# System_Voltage_Regulators.net
KiCad netlist of a schematic drawn in Altium Designer
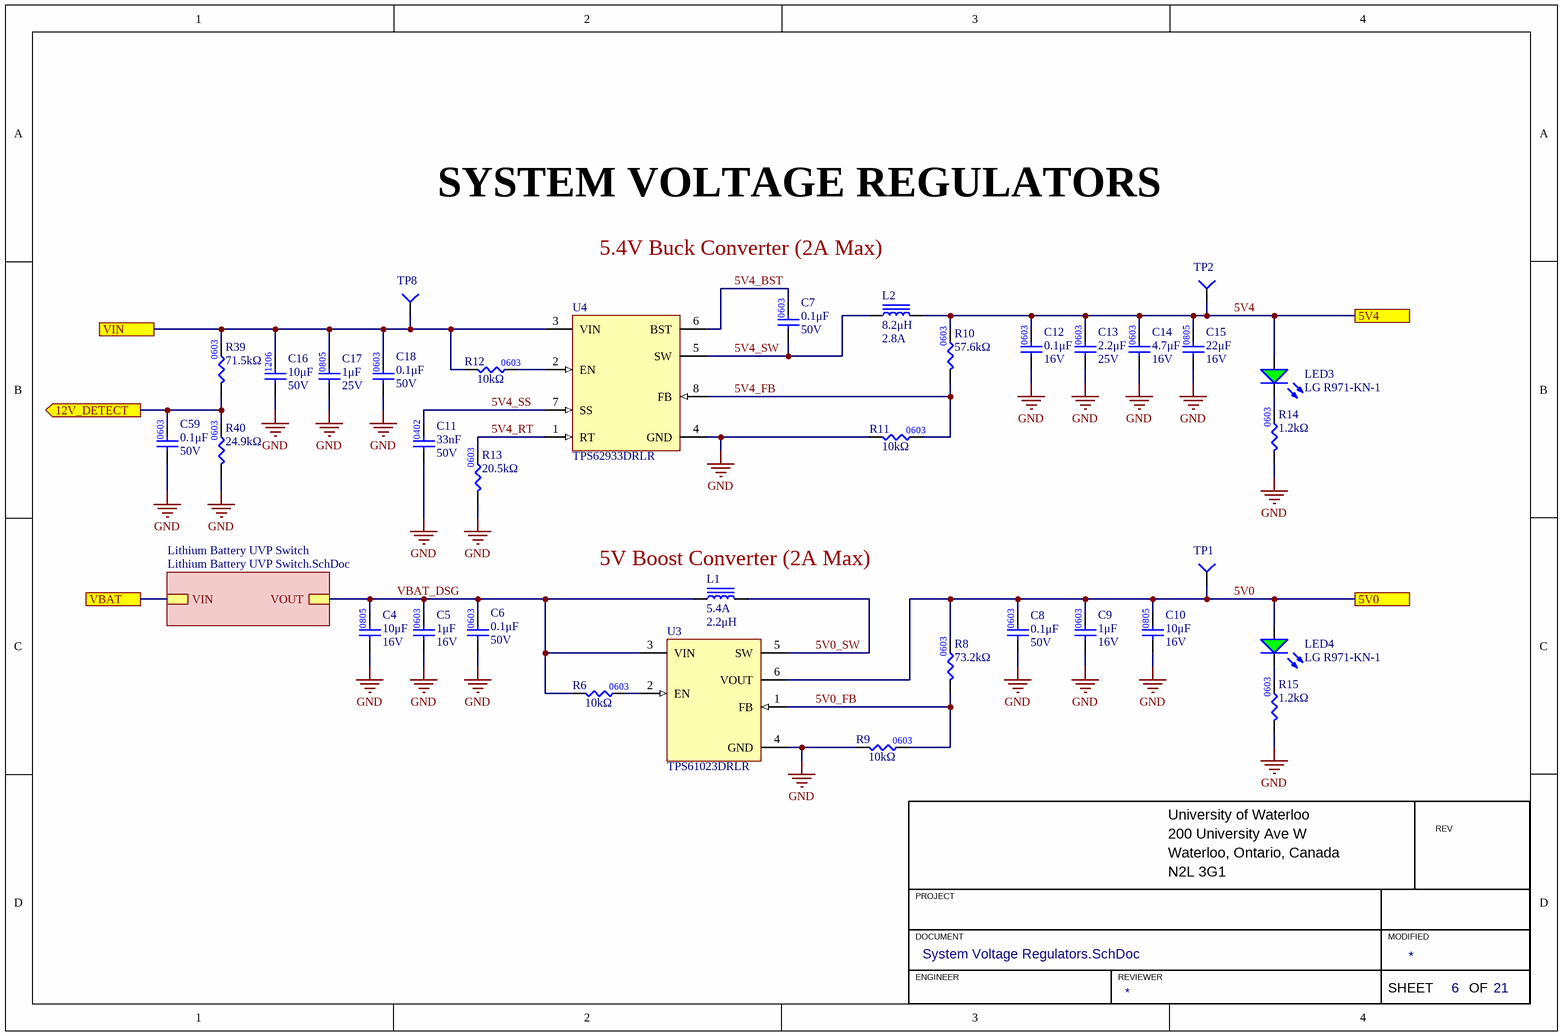
[diagram p0: System Voltage Regulators.SchDoc]

(export (version "E")
  (design (tool "Eeschema 10.0.6"))
  (components
    (comp (ref "C4")
      (value "10μF")
      (footprint "CAP0805")
      (description "CAP CER 10UF 16V X5R 0805")
      (fields (field (name "VOLTAGE RATING") "16V") (field (name "Comment") "CAP_10uF_16V_0805"))
      (libsource (lib "Personal_Schematic_Library_2022") (part "CAP_10uF_16V_0805"))
    )
    (comp (ref "C5")
      (value "1μF")
      (footprint "CAP0603")
      (description "CAP CER 1UF 16V X7R 0603")
      (fields (field (name "VOLTAGE RATING") "16V") (field (name "Comment") "CAP_1uF_16V_0603"))
      (libsource (lib "Personal_Schematic_Library_2022") (part "CAP_1uF_16V_0603"))
    )
    (comp (ref "C6")
      (value "0.1μF")
      (footprint "CAP0603")
      (description "CAP CER 0.1UF 50V X7R 0603")
      (fields (field (name "VOLTAGE RATING") "50V") (field (name "Comment") "CAP_0.1uF_50V_0603"))
      (libsource (lib "Personal_Schematic_Library_2022") (part "CAP_0.1uF_50V_0603"))
    )
    (comp (ref "C7")
      (value "0.1μF")
      (footprint "CAP0603")
      (description "CAP CER 0.1UF 50V X7R 0603")
      (fields (field (name "VOLTAGE RATING") "50V") (field (name "Comment") "CAP_0.1uF_50V_0603"))
      (libsource (lib "Personal_Schematic_Library_2022") (part "CAP_0.1uF_50V_0603"))
    )
    (comp (ref "C8")
      (value "0.1μF")
      (footprint "CAP0603")
      (description "CAP CER 0.1UF 50V X7R 0603")
      (fields (field (name "VOLTAGE RATING") "50V") (field (name "Comment") "CAP_0.1uF_50V_0603"))
      (libsource (lib "Personal_Schematic_Library_2022") (part "CAP_0.1uF_50V_0603"))
    )
    (comp (ref "C9")
      (value "1μF")
      (footprint "CAP0603")
      (description "CAP CER 1UF 16V X7R 0603")
      (fields (field (name "VOLTAGE RATING") "16V") (field (name "Comment") "CAP_1uF_16V_0603"))
      (libsource (lib "Personal_Schematic_Library_2022") (part "CAP_1uF_16V_0603"))
    )
    (comp (ref "C10")
      (value "10μF")
      (footprint "CAP0805")
      (description "CAP CER 10UF 16V X5R 0805")
      (fields (field (name "VOLTAGE RATING") "16V") (field (name "Comment") "CAP_10uF_16V_0805"))
      (libsource (lib "Personal_Schematic_Library_2022") (part "CAP_10uF_16V_0805"))
    )
    (comp (ref "C11")
      (value "CAP_0.033uF_50V_X7R_0603")
      (footprint "CAP0603")
      (description "CAP CER 0.033UF 50V X7R 0603")
      (fields
        (field (name "MANUFACTURER") "Samsung Electro-Mechanics")
        (field (name "MANUFACTURER PART NUMBER") "CL10B333KB8NFNC")
        (field (name "CAPACITANCE") "33nF")
        (field (name "RATED DC VOLTAGE (URDC)") "50V")
      )
      (libsource (lib "Personal_Schematic_Library_2022") (part "CAP_0.033uF_50V_X7R_0603"))
    )
    (comp (ref "C12")
      (value "0.1μF")
      (footprint "CAP0603")
      (description "CAP CER 0.1UF 16V X7R 0603")
      (fields (field (name "VOLTAGE RATING") "16V") (field (name "Comment") "CAP_0.1uF_16V_0603"))
      (libsource (lib "Personal_Schematic_Library_2022") (part "CAP_0.1uF_16V_0603"))
    )
    (comp (ref "C13")
      (value "2.2μF")
      (footprint "CAP0603")
      (description "CAP CER 2.2UF 25V X5R 0603")
      (fields (field (name "VOLTAGE RATING") "25V") (field (name "Comment") "CAP_2.2uF_25V_0603"))
      (libsource (lib "Personal_Schematic_Library_2022") (part "CAP_2.2uF_25V_0603"))
    )
    (comp (ref "C14")
      (value "4.7μF")
      (footprint "CAP0603")
      (description "CAP CER 4.7UF 16V X6S 0603")
      (fields (field (name "VOLTAGE RATING") "16V") (field (name "Comment") "CAP_4.7uF_16V_0603"))
      (libsource (lib "Personal_Schematic_Library_2022") (part "CAP_4.7uF_16V_0603"))
    )
    (comp (ref "C15")
      (value "22μF")
      (footprint "CAP0805")
      (description "CAP CER 22UF 16V X5R 0805")
      (fields (field (name "VOLTAGE RATING") "16V") (field (name "Comment") "CAP_22uF_16V_0805"))
      (libsource (lib "Personal_Schematic_Library_2022") (part "CAP_22uF_16V_0805"))
    )
    (comp (ref "C16")
      (value "10μF")
      (footprint "CAP1206")
      (description "CAP CER 10UF 50V X5R 1206")
      (fields (field (name "VOLTAGE RATING") "50V") (field (name "Comment") "CAP_10uF_50V_1206"))
      (libsource (lib "Personal_Schematic_Library_2022") (part "CAP_10uF_50V_1206"))
    )
    (comp (ref "C17")
      (value "1μF")
      (footprint "CAP0805")
      (description "CAP CER 1UF 25V X7R 0805")
      (fields (field (name "VOLTAGE RATING") "25V") (field (name "Comment") "CAP_1uF_25V_0805"))
      (libsource (lib "Personal_Schematic_Library_2022") (part "CAP_1uF_25V_0805"))
    )
    (comp (ref "C18")
      (value "0.1μF")
      (footprint "CAP0603")
      (description "CAP CER 0.1UF 50V X7R 0603")
      (fields (field (name "VOLTAGE RATING") "50V") (field (name "Comment") "CAP_0.1uF_50V_0603"))
      (libsource (lib "Personal_Schematic_Library_2022") (part "CAP_0.1uF_50V_0603"))
    )
    (comp (ref "C59")
      (value "0.1μF")
      (footprint "CAP0603")
      (description "CAP CER 0.1UF 50V X7R 0603")
      (fields (field (name "VOLTAGE RATING") "50V") (field (name "Comment") "CAP_0.1uF_50V_0603"))
      (libsource (lib "Personal_Schematic_Library_2022") (part "CAP_0.1uF_50V_0603"))
    )
    (comp (ref "L1")
      (value "IND_2.2uH_5.4A")
      (footprint "IND_1210")
      (description "FIXED IND 2.2UH 5.4A 46MOHM SMD")
      (fields (field (name "CURRENT RATING") "5.4A") (field (name "INDUCTANCE") "2.2μH"))
      (libsource (lib "Personal_Schematic_Library_2022") (part "IND_2.2uH_5.4A"))
    )
    (comp (ref "L2")
      (value "8.2μH")
      (footprint "IND_WURTH_1616")
      (description "FIXED IND 8.2UH 2.8A 86 MOHM SMD")
      (fields (field (name "CURRENT RATING") "2.8A") (field (name "Comment") "IND_8.2uH_2.8A"))
      (libsource (lib "Personal_Schematic_Library_2022") (part "IND_8.2uH_2.8A"))
    )
    (comp (ref "LED3")
      (value "LED_GREEN_0805")
      (footprint "LED_0805_GREEN")
      (description "LED GREEN DIFFUSED 0805 SMD")
      (fields (field (name "MANUFACTURER PART NUMBER 1") "LG R971-KN-1"))
      (libsource (lib "Personal_Schematic_Library_2022") (part "LED_GREEN_0805"))
    )
    (comp (ref "LED4")
      (value "LED_GREEN_0805")
      (footprint "LED_0805_GREEN")
      (description "LED GREEN DIFFUSED 0805 SMD")
      (fields (field (name "MANUFACTURER PART NUMBER 1") "LG R971-KN-1"))
      (libsource (lib "Personal_Schematic_Library_2022") (part "LED_GREEN_0805"))
    )
    (comp (ref "R6")
      (value "10kΩ")
      (footprint "RES0603")
      (description "RES 10K OHM 1% 1/8W 0603")
      (fields (field (name "Comment") "RES_10kΩ_0603_1%"))
      (libsource (lib "Personal_Schematic_Library_2022") (part "RES_10kΩ_0603_1%"))
    )
    (comp (ref "R8")
      (value "73.2kΩ")
      (footprint "RES0603")
      (description "RES 73.2K OHM 1% 1/16W 0603")
      (fields (field (name "Comment") "RES_73.2kΩ_0603_1%"))
      (libsource (lib "Personal_Schematic_Library_2022") (part "RES_73.2kΩ_0603_1%"))
    )
    (comp (ref "R9")
      (value "10kΩ")
      (footprint "RES0603")
      (description "RES 10K OHM 1% 1/8W 0603")
      (fields (field (name "Comment") "RES_10kΩ_0603_1%"))
      (libsource (lib "Personal_Schematic_Library_2022") (part "RES_10kΩ_0603_1%"))
    )
    (comp (ref "R10")
      (value "57.6kΩ")
      (footprint "RES0603")
      (description "RES 57.6K OHM 1% 1/10W 0603")
      (fields (field (name "Comment") "RES_57.6kΩ_0603_1%"))
      (libsource (lib "Personal_Schematic_Library_2022") (part "RES_57.6kΩ_0603_1%"))
    )
    (comp (ref "R11")
      (value "10kΩ")
      (footprint "RES0603")
      (description "RES 10K OHM 1% 1/8W 0603")
      (fields (field (name "Comment") "RES_10kΩ_0603_1%"))
      (libsource (lib "Personal_Schematic_Library_2022") (part "RES_10kΩ_0603_1%"))
    )
    (comp (ref "R12")
      (value "10kΩ")
      (footprint "RES0603")
      (description "RES 10K OHM 1% 1/8W 0603")
      (fields (field (name "Comment") "RES_10kΩ_0603_1%"))
      (libsource (lib "Personal_Schematic_Library_2022") (part "RES_10kΩ_0603_1%"))
    )
    (comp (ref "R13")
      (value "20.5kΩ")
      (footprint "RES0603")
      (description "RES SMD 20.5K OHM 1% 1/10W 0603")
      (fields (field (name "Comment") "RES_20.5kΩ_0603_1%"))
      (libsource (lib "Personal_Schematic_Library_2022") (part "RES_20.5kΩ_0603_1%"))
    )
    (comp (ref "R14")
      (value "1.2kΩ")
      (footprint "RES0603")
      (description "RES 1.2K OHM 1% 1/10W 0603")
      (fields (field (name "Comment") "RES_1.2kΩ_0603_1%"))
      (libsource (lib "Personal_Schematic_Library_2022") (part "RES_1.2kΩ_0603_1%"))
    )
    (comp (ref "R15")
      (value "1.2kΩ")
      (footprint "RES0603")
      (description "RES 1.2K OHM 1% 1/10W 0603")
      (fields (field (name "Comment") "RES_1.2kΩ_0603_1%"))
      (libsource (lib "Personal_Schematic_Library_2022") (part "RES_1.2kΩ_0603_1%"))
    )
    (comp (ref "R39")
      (value "71.5kΩ")
      (footprint "RES0603")
      (description "RES 71.5K OHM 1% 1/10W 0603")
      (fields (field (name "Comment") "RES_71.5kΩ_0603_1%"))
      (libsource (lib "Personal_Schematic_Library_2022") (part "RES_71.5kΩ_0603_1%"))
    )
    (comp (ref "R40")
      (value "24.9kΩ")
      (footprint "RES0603")
      (description "RES 24.9K OHM 1% 1/10W 0603")
      (fields (field (name "Comment") "RES_24.9kΩ_0603_1%"))
      (libsource (lib "Personal_Schematic_Library_2022") (part "RES_24.9kΩ_0603_1%"))
    )
    (comp (ref "TP1")
      (value "TESTPOINT_KEYSTONE_LOOP")
      (footprint "KEYSTONE_5019")
      (description "PC TEST POINT MINIATURE")
      (libsource (lib "Personal_Schematic_Library_2022") (part "TESTPOINT_KEYSTONE_LOOP"))
    )
    (comp (ref "TP2")
      (value "TESTPOINT_KEYSTONE_LOOP")
      (footprint "KEYSTONE_5019")
      (description "PC TEST POINT MINIATURE")
      (libsource (lib "Personal_Schematic_Library_2022") (part "TESTPOINT_KEYSTONE_LOOP"))
    )
    (comp (ref "TP8")
      (value "TESTPOINT_KEYSTONE_LOOP")
      (footprint "KEYSTONE_5019")
      (description "PC TEST POINT MINIATURE")
      (libsource (lib "Personal_Schematic_Library_2022") (part "TESTPOINT_KEYSTONE_LOOP"))
    )
    (comp (ref "U3")
      (value "TPS61023DRLR")
      (footprint "TI_SOT-563")
      (description "IC REG BOOST ADJ 3A SOT563")
      (libsource (lib "Personal_Schematic_Library_2022") (part "TPS61023DRLR"))
    )
    (comp (ref "U4")
      (value "TPS62933DRLR")
      (footprint "TI_SOT-583")
      (description "IC REG BUCK ADJ 3A SOT583")
      (libsource (lib "Personal_Schematic_Library_2022") (part "TPS62933DRLR"))
    )
  )
  (nets
    (net (code "1") (name "/5V0") (class "Default")
      (node (ref "C10") (pin "2") (pinfunction "2_2") (pintype "passive"))
      (node (ref "C8") (pin "2") (pinfunction "2_2") (pintype "passive"))
      (node (ref "C9") (pin "2") (pinfunction "2_2") (pintype "passive"))
      (node (ref "LED4") (pin "1") (pinfunction "A_1") (pintype "passive"))
      (node (ref "R8") (pin "2") (pinfunction "2_2") (pintype "passive"))
      (node (ref "TP1") (pin "1") (pinfunction "=value_1") (pintype "passive"))
      (node (ref "U3") (pin "6") (pinfunction "VOUT_6") (pintype "power_in"))
    )
    (net (code "2") (name "/5V0_FB") (class "Default")
      (node (ref "R8") (pin "1") (pinfunction "1_1") (pintype "passive"))
      (node (ref "R9") (pin "2") (pinfunction "2_2") (pintype "passive"))
      (node (ref "U3") (pin "1") (pinfunction "FB_1") (pintype "input"))
    )
    (net (code "3") (name "/5V0_SW") (class "Default")
      (node (ref "L1") (pin "2") (pinfunction "2_2") (pintype "passive"))
      (node (ref "U3") (pin "5") (pinfunction "SW_5") (pintype "power_in"))
    )
    (net (code "4") (name "/5V4") (class "Default")
      (node (ref "C12") (pin "2") (pinfunction "2_2") (pintype "passive"))
      (node (ref "C13") (pin "2") (pinfunction "2_2") (pintype "passive"))
      (node (ref "C14") (pin "2") (pinfunction "2_2") (pintype "passive"))
      (node (ref "C15") (pin "2") (pinfunction "2_2") (pintype "passive"))
      (node (ref "L2") (pin "2") (pinfunction "2_2") (pintype "passive"))
      (node (ref "LED3") (pin "1") (pinfunction "A_1") (pintype "passive"))
      (node (ref "R10") (pin "2") (pinfunction "2_2") (pintype "passive"))
      (node (ref "TP2") (pin "1") (pinfunction "=value_1") (pintype "passive"))
    )
    (net (code "5") (name "/5V4_BST") (class "Default")
      (node (ref "C7") (pin "2") (pinfunction "2_2") (pintype "passive"))
      (node (ref "U4") (pin "6") (pinfunction "BST_6") (pintype "power_in"))
    )
    (net (code "6") (name "/5V4_FB") (class "Default")
      (node (ref "R10") (pin "1") (pinfunction "1_1") (pintype "passive"))
      (node (ref "R11") (pin "2") (pinfunction "2_2") (pintype "passive"))
      (node (ref "U4") (pin "8") (pinfunction "FB_8") (pintype "input"))
    )
    (net (code "7") (name "/5V4_RT") (class "Default")
      (node (ref "R13") (pin "2") (pinfunction "2_2") (pintype "passive"))
      (node (ref "U4") (pin "1") (pinfunction "RT_1") (pintype "input"))
    )
    (net (code "8") (name "/5V4_SS") (class "Default")
      (node (ref "C11") (pin "2") (pinfunction "2_2") (pintype "passive"))
      (node (ref "U4") (pin "7") (pinfunction "SS_7") (pintype "input"))
    )
    (net (code "9") (name "/5V4_SW") (class "Default")
      (node (ref "C7") (pin "1") (pinfunction "1_1") (pintype "passive"))
      (node (ref "L2") (pin "1") (pinfunction "1_1") (pintype "passive"))
      (node (ref "U4") (pin "5") (pinfunction "SW_5") (pintype "power_in"))
    )
    (net (code "10") (name "/12V_DETECT") (class "Default")
      (node (ref "C59") (pin "2") (pinfunction "2_2") (pintype "passive"))
      (node (ref "R39") (pin "1") (pinfunction "1_1") (pintype "passive"))
      (node (ref "R40") (pin "2") (pinfunction "2_2") (pintype "passive"))
    )
    (net (code "12") (name "/VBAT_DSG") (class "Default")
      (node (ref "C4") (pin "2") (pinfunction "2_2") (pintype "passive"))
      (node (ref "C5") (pin "2") (pinfunction "2_2") (pintype "passive"))
      (node (ref "C6") (pin "2") (pinfunction "2_2") (pintype "passive"))
      (node (ref "L1") (pin "1") (pinfunction "1_1") (pintype "passive"))
      (node (ref "R6") (pin "1") (pinfunction "1_1") (pintype "passive"))
      (node (ref "U3") (pin "3") (pinfunction "VIN_3") (pintype "power_in"))
    )
    (net (code "13") (name "/VIN") (class "Default")
      (node (ref "C16") (pin "2") (pinfunction "2_2") (pintype "passive"))
      (node (ref "C17") (pin "2") (pinfunction "2_2") (pintype "passive"))
      (node (ref "C18") (pin "2") (pinfunction "2_2") (pintype "passive"))
      (node (ref "R12") (pin "1") (pinfunction "1_1") (pintype "passive"))
      (node (ref "R39") (pin "2") (pinfunction "2_2") (pintype "passive"))
      (node (ref "TP8") (pin "1") (pinfunction "=value_1") (pintype "passive"))
      (node (ref "U4") (pin "3") (pinfunction "VIN_3") (pintype "power_in"))
    )
    (net (code "14") (name "GND") (class "Default")
      (node (ref "C10") (pin "1") (pinfunction "1_1") (pintype "passive"))
      (node (ref "C11") (pin "1") (pinfunction "1_1") (pintype "passive"))
      (node (ref "C12") (pin "1") (pinfunction "1_1") (pintype "passive"))
      (node (ref "C13") (pin "1") (pinfunction "1_1") (pintype "passive"))
      (node (ref "C14") (pin "1") (pinfunction "1_1") (pintype "passive"))
      (node (ref "C15") (pin "1") (pinfunction "1_1") (pintype "passive"))
      (node (ref "C16") (pin "1") (pinfunction "1_1") (pintype "passive"))
      (node (ref "C17") (pin "1") (pinfunction "1_1") (pintype "passive"))
      (node (ref "C18") (pin "1") (pinfunction "1_1") (pintype "passive"))
      (node (ref "C4") (pin "1") (pinfunction "1_1") (pintype "passive"))
      (node (ref "C5") (pin "1") (pinfunction "1_1") (pintype "passive"))
      (node (ref "C59") (pin "1") (pinfunction "1_1") (pintype "passive"))
      (node (ref "C6") (pin "1") (pinfunction "1_1") (pintype "passive"))
      (node (ref "C8") (pin "1") (pinfunction "1_1") (pintype "passive"))
      (node (ref "C9") (pin "1") (pinfunction "1_1") (pintype "passive"))
      (node (ref "R11") (pin "1") (pinfunction "1_1") (pintype "passive"))
      (node (ref "R13") (pin "1") (pinfunction "1_1") (pintype "passive"))
      (node (ref "R14") (pin "1") (pinfunction "1_1") (pintype "passive"))
      (node (ref "R15") (pin "1") (pinfunction "1_1") (pintype "passive"))
      (node (ref "R40") (pin "1") (pinfunction "1_1") (pintype "passive"))
      (node (ref "R9") (pin "1") (pinfunction "1_1") (pintype "passive"))
      (node (ref "U3") (pin "4") (pinfunction "GND_4") (pintype "power_in"))
      (node (ref "U4") (pin "4") (pinfunction "GND_4") (pintype "power_in"))
    )
    (net (code "15") (name "Net-(LED3-K)") (class "Default")
      (node (ref "LED3") (pin "2") (pinfunction "K_2") (pintype "passive"))
      (node (ref "R14") (pin "2") (pinfunction "2_2") (pintype "passive"))
    )
    (net (code "16") (name "Net-(LED4-K)") (class "Default")
      (node (ref "LED4") (pin "2") (pinfunction "K_2") (pintype "passive"))
      (node (ref "R15") (pin "2") (pinfunction "2_2") (pintype "passive"))
    )
    (net (code "17") (name "Net-(U3-EN)") (class "Default")
      (node (ref "R6") (pin "2") (pinfunction "2_2") (pintype "passive"))
      (node (ref "U3") (pin "2") (pinfunction "EN_2") (pintype "input"))
    )
    (net (code "18") (name "Net-(U4-EN)") (class "Default")
      (node (ref "R12") (pin "2") (pinfunction "2_2") (pintype "passive"))
      (node (ref "U4") (pin "2") (pinfunction "EN_2") (pintype "input"))
    )
  )
)
